# PhotoInterrupter.net
KiCad netlist of a schematic drawn in EAGLE
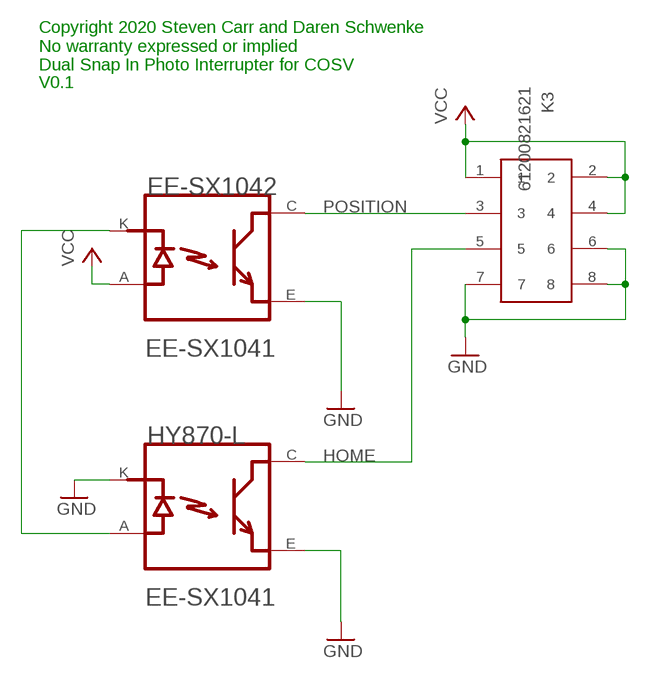
[diagram p0: schematic, sheet 1]

(export (version "E")
  (design (tool "Eeschema 10.0.6"))
  (components
    (comp (ref "EE-SX1042")
      (value "OMRON_ELECTRONICS_INC-EMC_DIV_EE-SX1041OMRON_ELECTRONICS_INC-EMC_DIV_EE-SX1041_0_0")
      (footprint "eagle-import:OMRON_ELECTRONICS_INC-EMC_DIV_EE-SX1041_0")
      (fields
        (field (name "DIGIKEY_PART_NUMBER") "OR625-ND")
        (field (name "MF") "Omron Electronics Inc-EMC Div")
        (field (name "MOUSER_PART_NUMBER") "653-EE-SX1041")
      )
      (libsource (lib "eagle-import") (part "OMRON_ELECTRONICS_INC-EMC_DIV_EE-SX1041OMRON_ELECTRONICS_INC-EMC_DIV_EE-SX1041_0_0"))
    )
    (comp (ref "HY870-L")
      (value "OMRON_ELECTRONICS_INC-EMC_DIV_EE-SX1041OMRON_ELECTRONICS_INC-EMC_DIV_EE-SX1041_0_0")
      (footprint "eagle-import:OMRON_ELECTRONICS_INC-EMC_DIV_EE-SX1041_0")
      (fields
        (field (name "DIGIKEY_PART_NUMBER") "OR625-ND")
        (field (name "MF") "Omron Electronics Inc-EMC Div")
        (field (name "MOUSER_PART_NUMBER") "653-EE-SX1041")
      )
      (libsource (lib "eagle-import") (part "OMRON_ELECTRONICS_INC-EMC_DIV_EE-SX1041OMRON_ELECTRONICS_INC-EMC_DIV_EE-SX1041_0_0"))
    )
    (comp (ref "K3")
      (value "61200821621")
      (footprint "eagle-import:61200821621")
      (libsource (lib "eagle-import") (part "61200821621"))
    )
  )
  (nets
    (net (code "1") (name "/HOME") (class "Default")
      (node (ref "HY870-L") (pin "C") (pinfunction "C_C") (pintype "passive"))
      (node (ref "K3") (pin "5") (pinfunction "5_5") (pintype "passive"))
    )
    (net (code "2") (name "/POSITION") (class "Default")
      (node (ref "EE-SX1042") (pin "C") (pinfunction "C_C") (pintype "passive"))
      (node (ref "K3") (pin "3") (pinfunction "3_3") (pintype "passive"))
    )
    (net (code "3") (name "GND") (class "Default")
      (node (ref "EE-SX1042") (pin "E") (pinfunction "E_E") (pintype "passive"))
      (node (ref "HY870-L") (pin "E") (pinfunction "E_E") (pintype "passive"))
      (node (ref "HY870-L") (pin "K") (pinfunction "K_K") (pintype "passive"))
      (node (ref "K3") (pin "6") (pinfunction "6_6") (pintype "passive"))
      (node (ref "K3") (pin "7") (pinfunction "7_7") (pintype "passive"))
      (node (ref "K3") (pin "8") (pinfunction "8_8") (pintype "passive"))
    )
    (net (code "4") (name "Net-(EE-SX1042-PadK)") (class "Default")
      (node (ref "EE-SX1042") (pin "K") (pinfunction "K_K") (pintype "passive"))
      (node (ref "HY870-L") (pin "A") (pinfunction "A_A") (pintype "passive"))
    )
    (net (code "5") (name "VCC") (class "Default")
      (node (ref "EE-SX1042") (pin "A") (pinfunction "A_A") (pintype "passive"))
      (node (ref "K3") (pin "1") (pinfunction "1_1") (pintype "passive"))
      (node (ref "K3") (pin "2") (pinfunction "2_2") (pintype "passive"))
      (node (ref "K3") (pin "4") (pinfunction "4_4") (pintype "passive"))
    )
  )
)
